# COMMUNICATION.net
KiCad netlist of a schematic drawn in Altium Designer
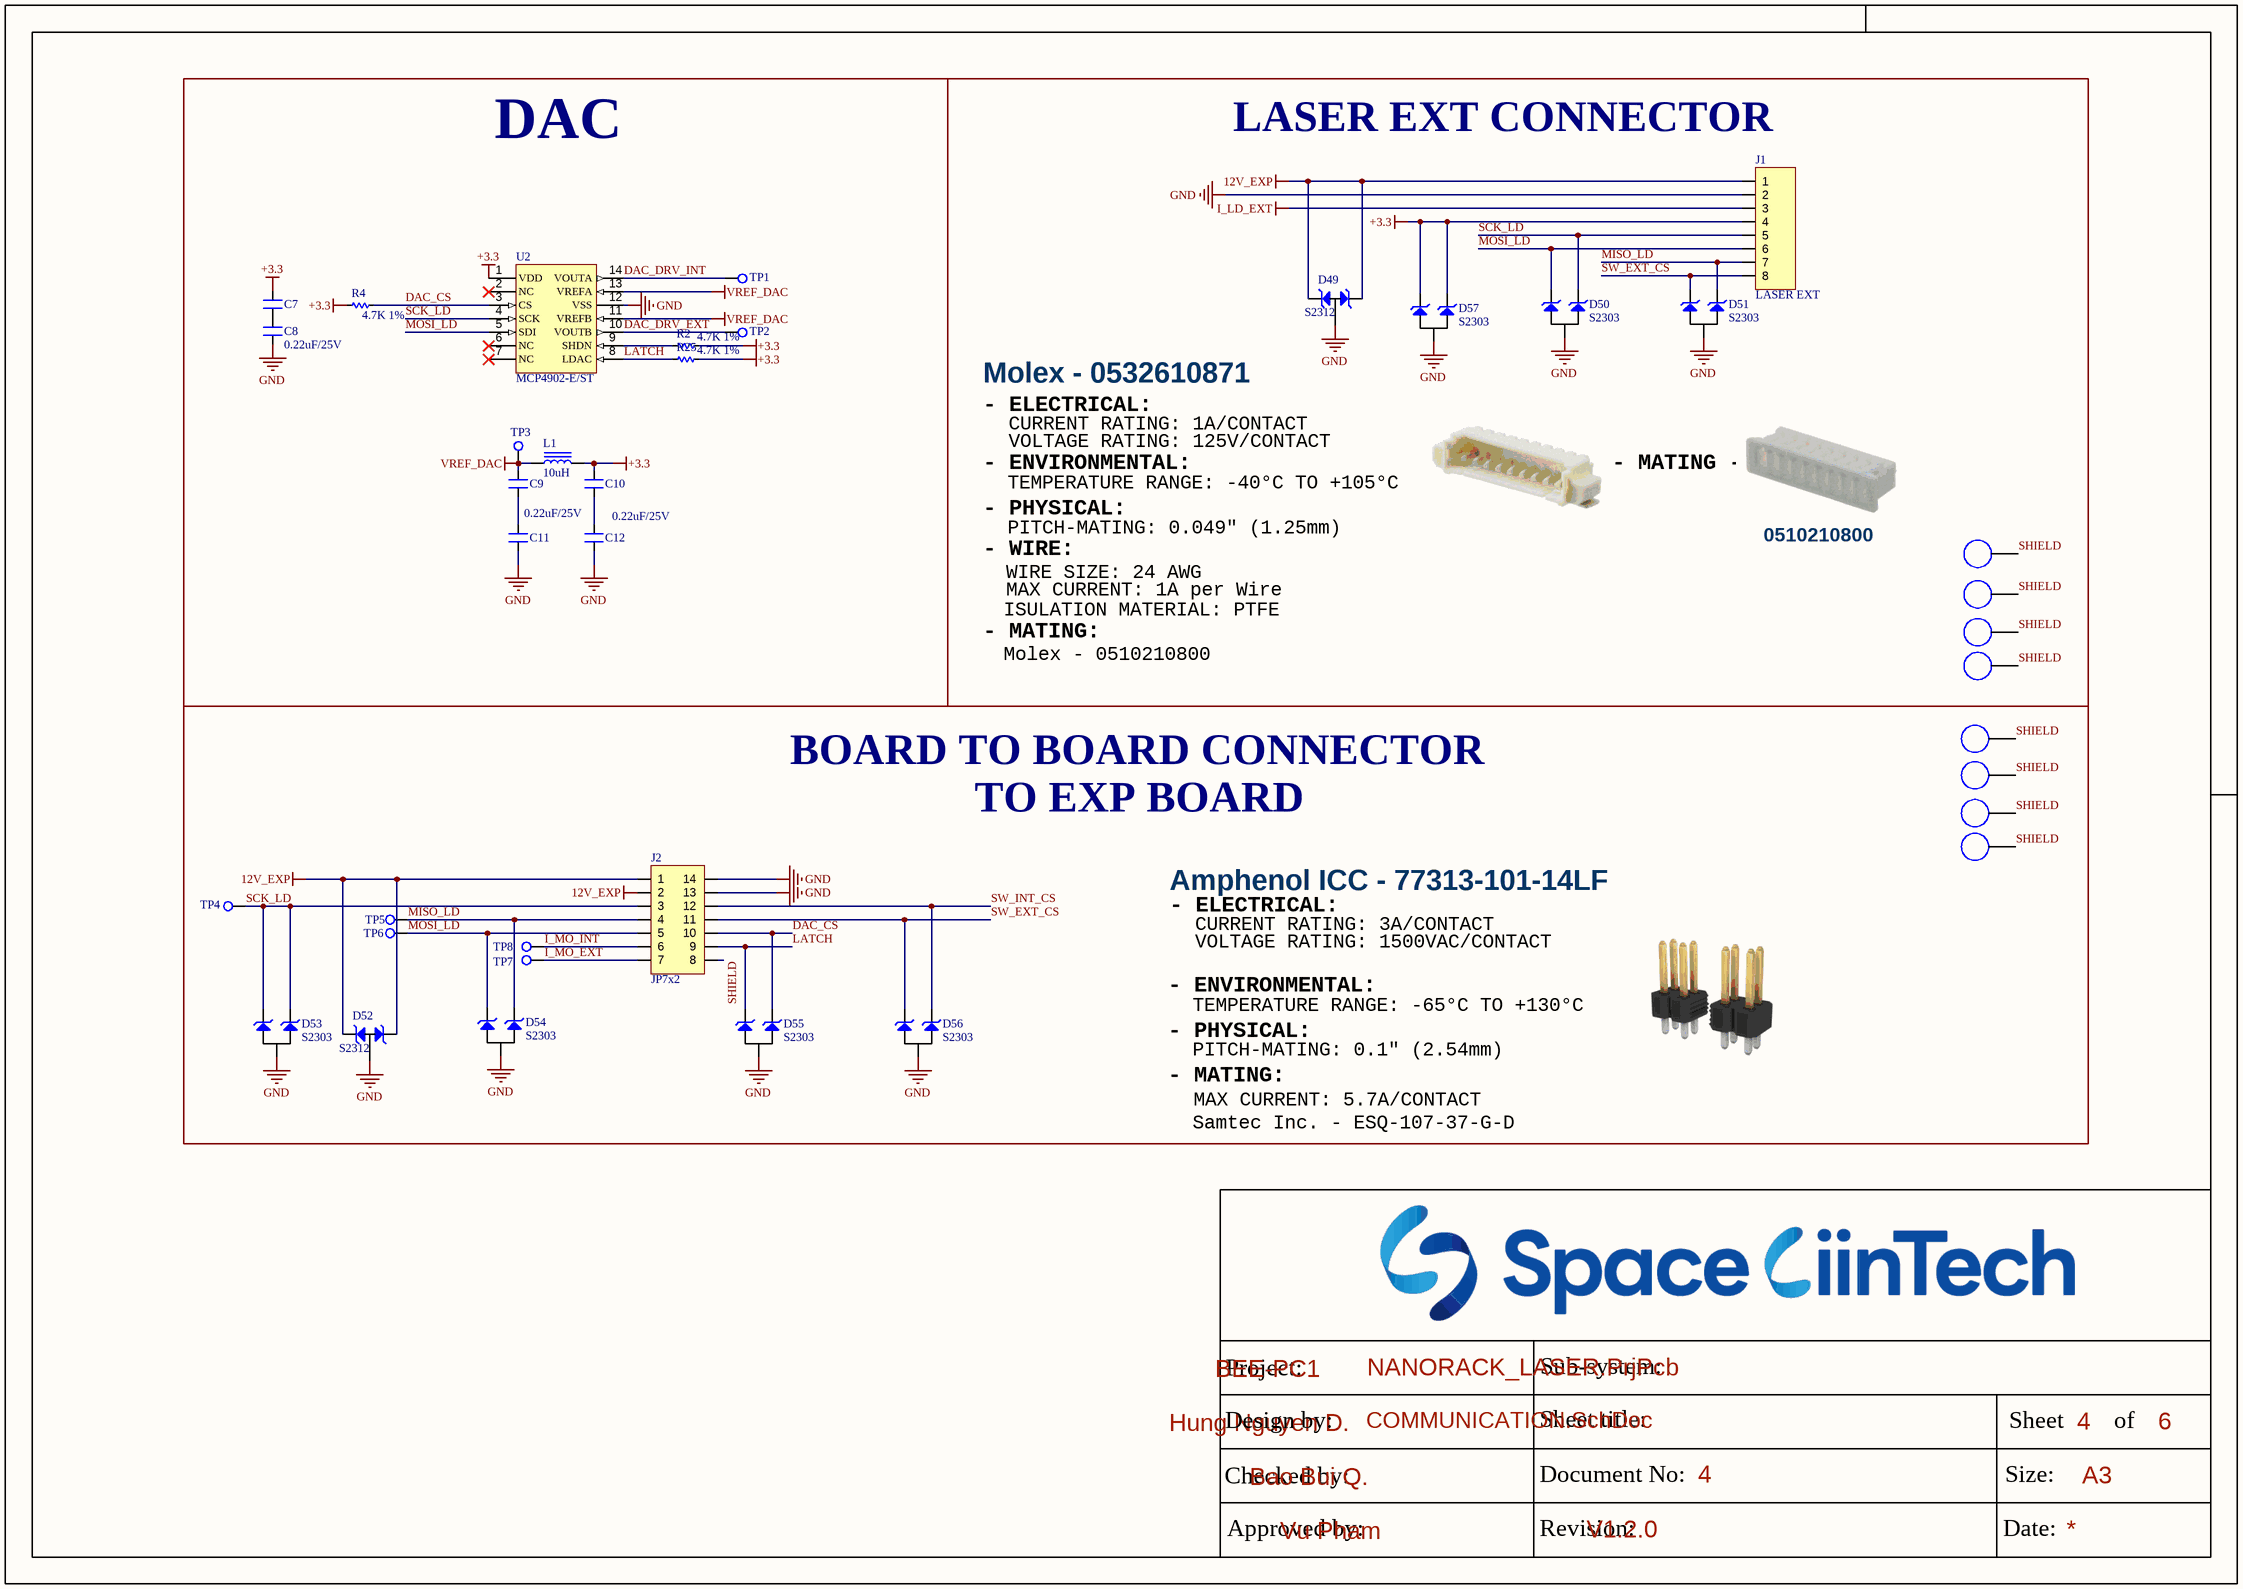
[diagram p0: COMMUNICATION.SchDoc]

(export (version "E")
  (design (tool "Eeschema 10.0.6"))
  (components
    (comp (ref "C7")
      (value "0.22uF/25V")
      (footprint "SM-0603")
      (description "0603")
      (libsource (lib "Capacitors") (part "CM"))
    )
    (comp (ref "C8")
      (value "0.22uF/25V")
      (footprint "SM-0603")
      (description "0603")
      (libsource (lib "Capacitors") (part "CM"))
    )
    (comp (ref "C9")
      (value "0.22uF/25V")
      (footprint "SM-0603")
      (description "0603")
      (libsource (lib "Capacitors") (part "CM"))
    )
    (comp (ref "C10")
      (value "0.22uF/25V")
      (footprint "SM-0603")
      (description "0603")
      (libsource (lib "Capacitors") (part "CM"))
    )
    (comp (ref "C11")
      (value "0.22uF/25V")
      (footprint "SM-0603")
      (description "0603")
      (libsource (lib "Capacitors") (part "CM"))
    )
    (comp (ref "C12")
      (value "0.22uF/25V")
      (footprint "SM-0603")
      (description "0603")
      (libsource (lib "Capacitors") (part "CM"))
    )
    (comp (ref "D49")
      (value "S2312")
      (footprint "SOT23-123")
      (description "TVS DIODE 12VWM 19VC SOT23, P/N:  S2312")
      (libsource (lib "Library") (part "S2315"))
    )
    (comp (ref "D50")
      (value "S2303")
      (footprint "SOT23-123")
      (description "TVS DIODE 3.3VWM 8VC SOT23, P/N:  \r\nS2303")
      (libsource (lib "Library") (part "S2303"))
    )
    (comp (ref "D51")
      (value "S2303")
      (footprint "SOT23-123")
      (description "TVS DIODE 3.3VWM 8VC SOT23, P/N:  \r\nS2303")
      (libsource (lib "Library") (part "S2303"))
    )
    (comp (ref "D52")
      (value "S2312")
      (footprint "SOT23-123")
      (description "TVS DIODE 12VWM 19VC SOT23, P/N:  S2312")
      (libsource (lib "Library") (part "S2315"))
    )
    (comp (ref "D53")
      (value "S2303")
      (footprint "SOT23-123")
      (description "TVS DIODE 3.3VWM 8VC SOT23, P/N:  \r\nS2303")
      (libsource (lib "Library") (part "S2303"))
    )
    (comp (ref "D54")
      (value "S2303")
      (footprint "SOT23-123")
      (description "TVS DIODE 3.3VWM 8VC SOT23, P/N:  \r\nS2303")
      (libsource (lib "Library") (part "S2303"))
    )
    (comp (ref "D55")
      (value "S2303")
      (footprint "SOT23-123")
      (description "TVS DIODE 3.3VWM 8VC SOT23, P/N:  \r\nS2303")
      (libsource (lib "Library") (part "S2303"))
    )
    (comp (ref "D56")
      (value "S2303")
      (footprint "SOT23-123")
      (description "TVS DIODE 3.3VWM 8VC SOT23, P/N:  \r\nS2303")
      (libsource (lib "Library") (part "S2303"))
    )
    (comp (ref "D57")
      (value "S2303")
      (footprint "SOT23-123")
      (description "TVS DIODE 3.3VWM 8VC SOT23, P/N:  \r\nS2303")
      (libsource (lib "Library") (part "S2303"))
    )
    (comp (ref "H1") (value "HOLD") (footprint "M3") (libsource (lib "Library_HUNG") (part "PAD_HOLD")))
    (comp (ref "H2") (value "HOLD") (footprint "M3") (libsource (lib "Library_HUNG") (part "PAD_HOLD")))
    (comp (ref "H3") (value "HOLD") (footprint "M3") (libsource (lib "Library_HUNG") (part "PAD_HOLD")))
    (comp (ref "H4") (value "HOLD") (footprint "M3") (libsource (lib "Library_HUNG") (part "PAD_HOLD")))
    (comp (ref "H5") (value "HOLD") (footprint "M3") (libsource (lib "Library_HUNG") (part "PAD_HOLD")))
    (comp (ref "H6") (value "HOLD") (footprint "M3") (libsource (lib "Library_HUNG") (part "PAD_HOLD")))
    (comp (ref "H7") (value "HOLD") (footprint "M3") (libsource (lib "Library_HUNG") (part "PAD_HOLD")))
    (comp (ref "H8") (value "HOLD") (footprint "M3") (libsource (lib "Library_HUNG") (part "PAD_HOLD")))
    (comp (ref "J1")
      (value "LASER EXT")
      (footprint "0532610871")
      (description "WR-PHD 2.54 mm Angled Socket Header")
      (fields
        (field (name "MANUFACTURER") "Würth Elektronik eiSos GmbH")
        (field (name "PARTNO") "613008143121")
        (field (name "CREATED BY") "Karrer Zheng")
      )
      (libsource (lib "Library_HUNG") (part "JP8"))
    )
    (comp (ref "J2")
      (value "JP7x2")
      (footprint "JP7-D2T")
      (description "WR-PHD 2.54 mm Dual Socket Header")
      (fields
        (field (name "MANUFACTURER") "Würth Elektronik eiSos GmbH")
        (field (name "PARTNO") "61301421821")
        (field (name "CREATED BY") "Karrer Zheng")
      )
      (libsource (lib "Library") (part "JP7x2"))
    )
    (comp (ref "L1")
      (value "10uH")
      (footprint "FER 0805/2012")
      (description "MLZ1608N100LT000")
      (libsource (lib "INDUCTOR") (part "Inductor"))
    )
    (comp (ref "R2")
      (value "4.7K 1%")
      (footprint "RES-SMD-0603")
      (description "0603")
      (fields
        (field (name "MANUFACTURER") "Generic Components")
        (field (name "PUBLISHER") "Altium Hobart Technology Centre")
      )
      (libsource (lib "Library") (part "Res-SMD"))
    )
    (comp (ref "R4")
      (value "4.7K 1%")
      (footprint "RES-SMD-0603")
      (description "0603")
      (fields
        (field (name "MANUFACTURER") "Generic Components")
        (field (name "PUBLISHER") "Altium Hobart Technology Centre")
      )
      (libsource (lib "Library") (part "Res-SMD"))
    )
    (comp (ref "R25")
      (value "4.7K 1%")
      (footprint "RES-SMD-0603")
      (description "0603")
      (fields
        (field (name "MANUFACTURER") "Generic Components")
        (field (name "PUBLISHER") "Altium Hobart Technology Centre")
      )
      (libsource (lib "Library") (part "Res-SMD"))
    )
    (comp (ref "TP1")
      (value "Test_Point")
      (footprint "TESTPOINT")
      (libsource (lib "Library_HUNG") (part "Test_Point"))
    )
    (comp (ref "TP2")
      (value "Test_Point")
      (footprint "TESTPOINT")
      (libsource (lib "Library_HUNG") (part "Test_Point"))
    )
    (comp (ref "TP3")
      (value "Test_Point")
      (footprint "TESTPOINT")
      (libsource (lib "Library_HUNG") (part "Test_Point"))
    )
    (comp (ref "TP4")
      (value "Test_Point")
      (footprint "TESTPOINT")
      (libsource (lib "Library_HUNG") (part "Test_Point"))
    )
    (comp (ref "TP5")
      (value "Test_Point")
      (footprint "TESTPOINT")
      (libsource (lib "Library_HUNG") (part "Test_Point"))
    )
    (comp (ref "TP6")
      (value "Test_Point")
      (footprint "TESTPOINT")
      (libsource (lib "Library_HUNG") (part "Test_Point"))
    )
    (comp (ref "TP7")
      (value "Test_Point")
      (footprint "TESTPOINT")
      (libsource (lib "Library_HUNG") (part "Test_Point"))
    )
    (comp (ref "TP8")
      (value "Test_Point")
      (footprint "TESTPOINT")
      (libsource (lib "Library_HUNG") (part "Test_Point"))
    )
    (comp (ref "U2")
      (value "MCP4902-E/ST")
      (footprint "TSSOP14")
      (description "IC DAC 8BIT V-OUT 14TSSOP")
      (libsource (lib "Library") (part "MCP4902"))
    )
  )
  (nets
    (net (code "1") (name "+3.3") (class "Default")
      (node (ref "C10") (pin "2") (pinfunction "2_2") (pintype "passive"))
      (node (ref "C7") (pin "2") (pinfunction "2_2") (pintype "passive"))
      (node (ref "D57") (pin "1") (pintype "passive"))
      (node (ref "D57") (pin "3") (pintype "passive"))
      (node (ref "J1") (pin "4") (pinfunction "4_4") (pintype "passive"))
      (node (ref "L1") (pin "2") (pinfunction "2_2") (pintype "passive"))
      (node (ref "R2") (pin "1") (pinfunction "1_1") (pintype "passive"))
      (node (ref "R25") (pin "1") (pinfunction "1_1") (pintype "passive"))
      (node (ref "R4") (pin "2") (pinfunction "2_2") (pintype "passive"))
      (node (ref "U2") (pin "1") (pinfunction "VDD_1") (pintype "power_in"))
    )
    (net (code "2") (name "/DAC_CS") (class "Default")
      (node (ref "D55") (pin "3") (pintype "passive"))
      (node (ref "J2") (pin "10") (pinfunction "10_10") (pintype "passive"))
      (node (ref "R4") (pin "1") (pinfunction "1_1") (pintype "passive"))
      (node (ref "U2") (pin "3") (pinfunction "CS_3") (pintype "input"))
    )
    (net (code "3") (name "/DAC_DRV_EXT") (class "Default")
      (node (ref "TP2") (pin "1") (pintype "power_in"))
      (node (ref "U2") (pin "10") (pinfunction "VOUTB_10") (pintype "output"))
    )
    (net (code "4") (name "/DAC_DRV_INT") (class "Default")
      (node (ref "TP1") (pin "1") (pintype "power_in"))
      (node (ref "U2") (pin "14") (pinfunction "VOUTA_14") (pintype "output"))
    )
    (net (code "5") (name "/I_MO_EXT") (class "Default")
      (node (ref "J2") (pin "7") (pinfunction "7_7") (pintype "passive"))
      (node (ref "TP7") (pin "1") (pintype "power_in"))
    )
    (net (code "6") (name "/I_MO_INT") (class "Default")
      (node (ref "J2") (pin "6") (pinfunction "6_6") (pintype "passive"))
      (node (ref "TP8") (pin "1") (pintype "power_in"))
    )
    (net (code "7") (name "/LATCH") (class "Default")
      (node (ref "D55") (pin "1") (pintype "passive"))
      (node (ref "J2") (pin "9") (pinfunction "9_9") (pintype "passive"))
      (node (ref "R25") (pin "2") (pinfunction "2_2") (pintype "passive"))
      (node (ref "U2") (pin "8") (pinfunction "LDAC_8") (pintype "input"))
    )
    (net (code "8") (name "/MISO_LD") (class "Default")
      (node (ref "D51") (pin "3") (pintype "passive"))
      (node (ref "D54") (pin "3") (pintype "passive"))
      (node (ref "J1") (pin "7") (pinfunction "7_7") (pintype "passive"))
      (node (ref "J2") (pin "4") (pinfunction "4_4") (pintype "passive"))
      (node (ref "TP5") (pin "1") (pintype "power_in"))
    )
    (net (code "9") (name "/MOSI_LD") (class "Default")
      (node (ref "D50") (pin "1") (pintype "passive"))
      (node (ref "D54") (pin "1") (pintype "passive"))
      (node (ref "J1") (pin "6") (pinfunction "6_6") (pintype "passive"))
      (node (ref "J2") (pin "5") (pinfunction "5_5") (pintype "passive"))
      (node (ref "TP6") (pin "1") (pintype "power_in"))
      (node (ref "U2") (pin "5") (pinfunction "SDI_5") (pintype "input"))
    )
    (net (code "10") (name "/SCK_LD") (class "Default")
      (node (ref "D50") (pin "3") (pintype "passive"))
      (node (ref "D53") (pin "1") (pintype "passive"))
      (node (ref "D53") (pin "3") (pintype "passive"))
      (node (ref "J1") (pin "5") (pinfunction "5_5") (pintype "passive"))
      (node (ref "J2") (pin "3") (pinfunction "3_3") (pintype "passive"))
      (node (ref "TP4") (pin "1") (pintype "power_in"))
      (node (ref "U2") (pin "4") (pinfunction "SCK_4") (pintype "input"))
    )
    (net (code "11") (name "/SHIELD") (class "Default")
      (node (ref "H1") (pin "1") (pintype "power_in"))
      (node (ref "H2") (pin "1") (pintype "power_in"))
      (node (ref "H3") (pin "1") (pintype "power_in"))
      (node (ref "H4") (pin "1") (pintype "power_in"))
      (node (ref "H5") (pin "1") (pintype "power_in"))
      (node (ref "H6") (pin "1") (pintype "power_in"))
      (node (ref "H7") (pin "1") (pintype "power_in"))
      (node (ref "H8") (pin "1") (pintype "power_in"))
      (node (ref "J2") (pin "8") (pinfunction "8_8") (pintype "passive"))
    )
    (net (code "12") (name "/SW_EXT_CS") (class "Default")
      (node (ref "D51") (pin "1") (pintype "passive"))
      (node (ref "D56") (pin "1") (pintype "passive"))
      (node (ref "J1") (pin "8") (pinfunction "8_8") (pintype "passive"))
      (node (ref "J2") (pin "11") (pinfunction "11_11") (pintype "passive"))
    )
    (net (code "13") (name "/SW_INT_CS") (class "Default")
      (node (ref "D56") (pin "3") (pintype "passive"))
      (node (ref "J2") (pin "12") (pinfunction "12_12") (pintype "passive"))
    )
    (net (code "14") (name "12V_EXP") (class "Default")
      (node (ref "D49") (pin "1") (pintype "passive"))
      (node (ref "D49") (pin "3") (pintype "passive"))
      (node (ref "D52") (pin "1") (pintype "passive"))
      (node (ref "D52") (pin "3") (pintype "passive"))
      (node (ref "J1") (pin "1") (pinfunction "1_1") (pintype "passive"))
      (node (ref "J2") (pin "1") (pinfunction "1_1") (pintype "passive"))
      (node (ref "J2") (pin "2") (pinfunction "2_2") (pintype "passive"))
    )
    (net (code "15") (name "GND") (class "Default")
      (node (ref "C11") (pin "1") (pinfunction "1_1") (pintype "passive"))
      (node (ref "C12") (pin "1") (pinfunction "1_1") (pintype "passive"))
      (node (ref "C8") (pin "1") (pinfunction "1_1") (pintype "passive"))
      (node (ref "D49") (pin "2") (pintype "passive"))
      (node (ref "D50") (pin "2") (pintype "passive"))
      (node (ref "D51") (pin "2") (pintype "passive"))
      (node (ref "D52") (pin "2") (pintype "passive"))
      (node (ref "D53") (pin "2") (pintype "passive"))
      (node (ref "D54") (pin "2") (pintype "passive"))
      (node (ref "D55") (pin "2") (pintype "passive"))
      (node (ref "D56") (pin "2") (pintype "passive"))
      (node (ref "D57") (pin "2") (pintype "passive"))
      (node (ref "J1") (pin "2") (pinfunction "2_2") (pintype "passive"))
      (node (ref "J2") (pin "13") (pinfunction "13_13") (pintype "passive"))
      (node (ref "J2") (pin "14") (pinfunction "14_14") (pintype "passive"))
      (node (ref "U2") (pin "12") (pinfunction "VSS_12") (pintype "power_in"))
    )
    (net (code "16") (name "I_LD_EXT") (class "Default")
      (node (ref "J1") (pin "3") (pinfunction "3_3") (pintype "passive"))
    )
    (net (code "17") (name "Net-(C7-Pad1)") (class "Default")
      (node (ref "C7") (pin "1") (pinfunction "1_1") (pintype "passive"))
      (node (ref "C8") (pin "2") (pinfunction "2_2") (pintype "passive"))
    )
    (net (code "18") (name "Net-(C10-Pad1)") (class "Default")
      (node (ref "C10") (pin "1") (pinfunction "1_1") (pintype "passive"))
      (node (ref "C12") (pin "2") (pinfunction "2_2") (pintype "passive"))
    )
    (net (code "19") (name "Net-(C11-Pad2)") (class "Default")
      (node (ref "C11") (pin "2") (pinfunction "2_2") (pintype "passive"))
      (node (ref "C9") (pin "1") (pinfunction "1_1") (pintype "passive"))
    )
    (net (code "20") (name "Net-(U2-SHDN)") (class "Default")
      (node (ref "R2") (pin "2") (pinfunction "2_2") (pintype "passive"))
      (node (ref "U2") (pin "9") (pinfunction "SHDN_9") (pintype "input"))
    )
    (net (code "21") (name "VREF_DAC") (class "Default")
      (node (ref "C9") (pin "2") (pinfunction "2_2") (pintype "passive"))
      (node (ref "L1") (pin "1") (pinfunction "1_1") (pintype "passive"))
      (node (ref "TP3") (pin "1") (pintype "power_in"))
      (node (ref "U2") (pin "11") (pinfunction "VREFB_11") (pintype "input"))
      (node (ref "U2") (pin "13") (pinfunction "VREFA_13") (pintype "input"))
    )
    (net (code "22") (name "unconnected-(U2-NC-Pad2)") (class "Default")
      (node (ref "U2") (pin "2") (pinfunction "NC_2") (pintype "tri_state+no_connect"))
    )
    (net (code "23") (name "unconnected-(U2-NC-Pad6)") (class "Default")
      (node (ref "U2") (pin "6") (pinfunction "NC_6") (pintype "tri_state+no_connect"))
    )
    (net (code "24") (name "unconnected-(U2-NC-Pad7)") (class "Default")
      (node (ref "U2") (pin "7") (pinfunction "NC_7") (pintype "tri_state+no_connect"))
    )
  )
)
